# BLE-NTC.net
KiCad netlist of a schematic drawn in Altium Designer
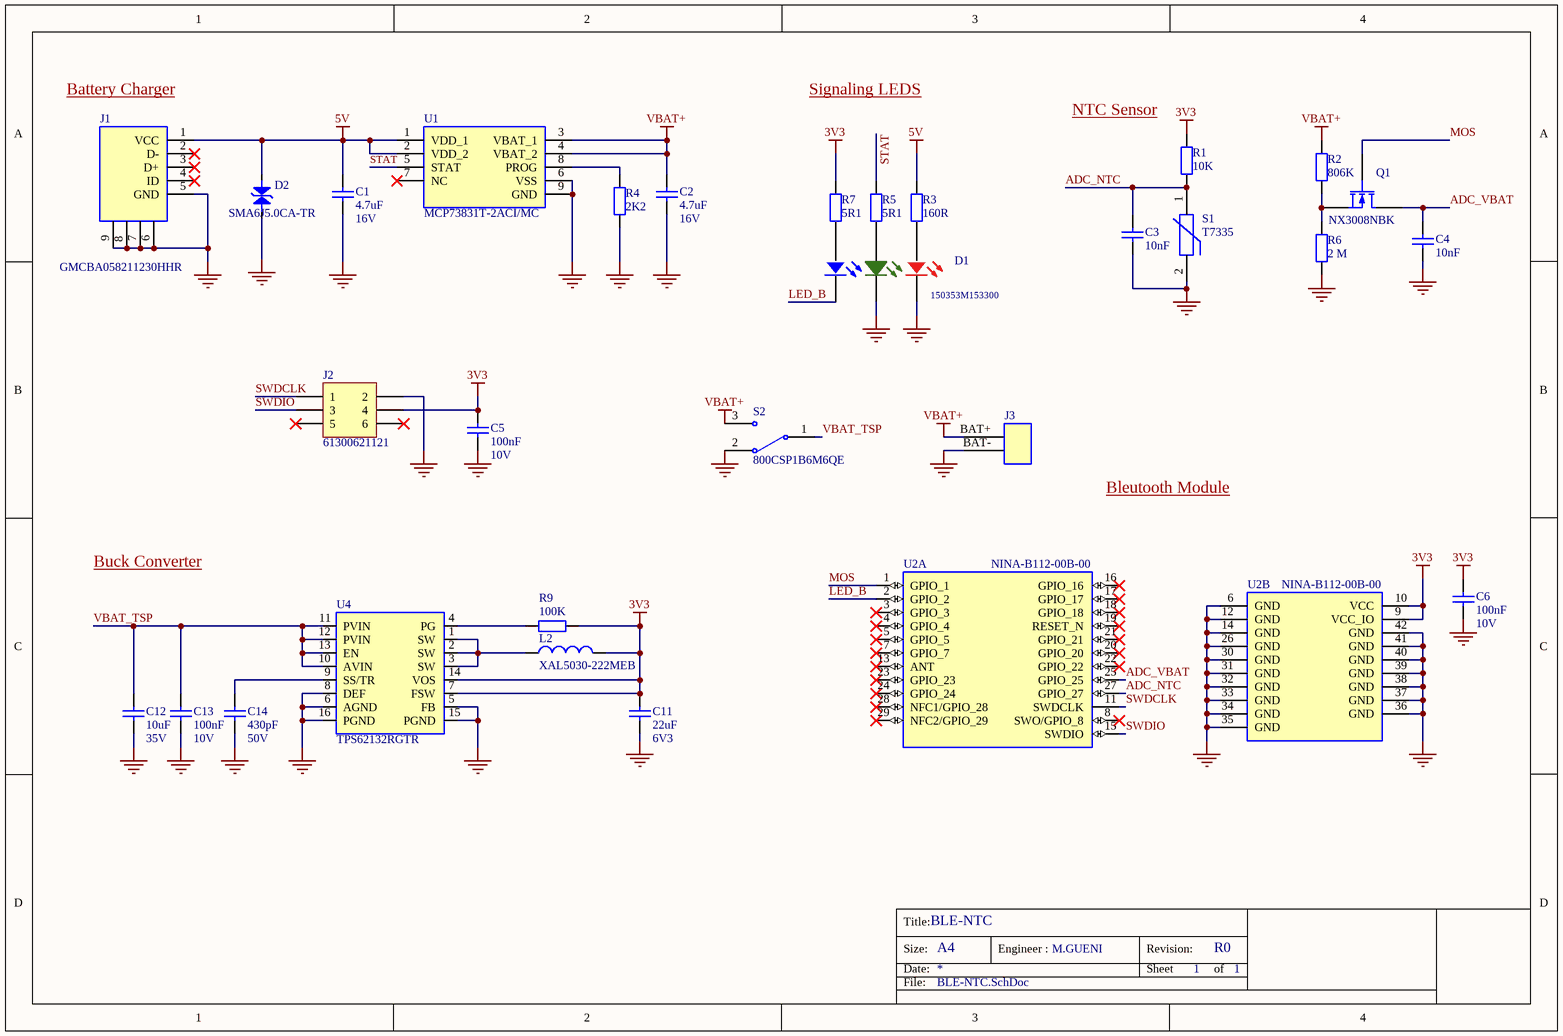
[diagram p0: BLE-NTC.SchDoc]

(export (version "E")
  (design (tool "Eeschema 10.0.6"))
  (components
    (comp (ref "C1")
      (value "Capacitor")
      (footprint "CAPC1608N")
      (fields
        (field (name "PART NUMBER") "CAP-000000047")
        (field (name "VALUE 1") "4.7uF")
        (field (name "VALUE 2") "16V")
      )
      (libsource (lib "Database_Libs1") (part "Capacitor"))
    )
    (comp (ref "C2")
      (value "Capacitor")
      (footprint "CAPC1608N")
      (fields
        (field (name "PART NUMBER") "CAP-000000047")
        (field (name "VALUE 1") "4.7uF")
        (field (name "VALUE 2") "16V")
      )
      (libsource (lib "Database_Libs1") (part "Capacitor"))
    )
    (comp (ref "C3")
      (value "Capacitor")
      (footprint "CAPC1608N")
      (fields (field (name "PART NUMBER") "CAP-000000003") (field (name "VALUE 1") "10nF"))
      (libsource (lib "Database_Libs1") (part "Capacitor"))
    )
    (comp (ref "C4")
      (value "Capacitor")
      (footprint "CAPC1608N")
      (fields (field (name "PART NUMBER") "CAP-000000003") (field (name "VALUE 1") "10nF"))
      (libsource (lib "Database_Libs1") (part "Capacitor"))
    )
    (comp (ref "C5")
      (value "Capacitor")
      (footprint "CAPC1608N")
      (fields
        (field (name "PART NUMBER") "CAP-000000005")
        (field (name "VALUE 1") "100nF")
        (field (name "VALUE 2") "10V")
      )
      (libsource (lib "Database_Libs1") (part "Capacitor"))
    )
    (comp (ref "C6")
      (value "Capacitor")
      (footprint "CAPC1608N")
      (fields
        (field (name "PART NUMBER") "CAP-000000005")
        (field (name "VALUE 1") "100nF")
        (field (name "VALUE 2") "10V")
      )
      (libsource (lib "Database_Libs1") (part "Capacitor"))
    )
    (comp (ref "C11")
      (value "Capacitor")
      (footprint "CAPC1608N")
      (fields
        (field (name "PART NUMBER") "CAP-000000045")
        (field (name "VALUE 1") "22uF")
        (field (name "VALUE 2") "6V3")
      )
      (libsource (lib "Database_Libs1") (part "Capacitor"))
    )
    (comp (ref "C12")
      (value "Capacitor")
      (footprint "CAPC1608N")
      (fields
        (field (name "PART NUMBER") "CAP-000000006")
        (field (name "VALUE 1") "10uF")
        (field (name "VALUE 2") "35V")
      )
      (libsource (lib "Database_Libs1") (part "Capacitor"))
    )
    (comp (ref "C13")
      (value "Capacitor")
      (footprint "CAPC1608N")
      (fields
        (field (name "PART NUMBER") "CAP-000000005")
        (field (name "VALUE 1") "100nF")
        (field (name "VALUE 2") "10V")
      )
      (libsource (lib "Database_Libs1") (part "Capacitor"))
    )
    (comp (ref "C14")
      (value "Capacitor")
      (footprint "CAPC1608N")
      (fields
        (field (name "PART NUMBER") "CAP-000000044")
        (field (name "VALUE 1") "430pF")
        (field (name "VALUE 2") "50V")
      )
      (libsource (lib "Database_Libs1") (part "Capacitor"))
    )
    (comp (ref "D1")
      (value "150353M153300")
      (footprint "150353M153300")
      (fields (field (name "PART NUMBER") "LED-000000004"))
      (libsource (lib "Database_Libs1") (part "150353M153300"))
    )
    (comp (ref "D2")
      (value "SMA6J5.0CA-TR")
      (footprint "SMA6J5.0CA-TR")
      (fields (field (name "PART NUMBER") "TVS-000000006"))
      (libsource (lib "Database_Libs1") (part "TVS0"))
    )
    (comp (ref "J1")
      (value "GMCBA058211230HHR")
      (footprint "GMCBA058211230HHR")
      (fields (field (name "PART NUMBER") "CON-000000037"))
      (libsource (lib "Database_Libs1") (part "USB"))
    )
    (comp (ref "J2")
      (value "61300621121")
      (footprint "HDR2X3")
      (fields (field (name "PART NUMBER") "CON-000000012"))
      (libsource (lib "Database_Libs1") (part "Header 2X3"))
    )
    (comp (ref "J3")
      (value "BAT_PAD")
      (footprint "BAT_PAD")
      (fields (field (name "PART NUMBER") "MIS-000000024"))
      (libsource (lib "Database_Libs1") (part "BAT_PAD"))
    )
    (comp (ref "L2")
      (value "XAL5030-222MEB")
      (footprint "22uh-XAL5030")
      (fields (field (name "PART NUMBER") "IND-000000001"))
      (libsource (lib "Database_Libs1") (part "Inductor"))
    )
    (comp (ref "Q1")
      (value "NX3008NBK")
      (footprint "SOT23-3N")
      (fields (field (name "PART NUMBER") "TRM-000000001"))
      (libsource (lib "Database_Libs1") (part "MOSFET-N-0"))
    )
    (comp (ref "R1")
      (value "Resistor")
      (footprint "RESC1608N")
      (fields (field (name "PART NUMBER") "RES-000000001") (field (name "VALUE 1") "10K"))
      (libsource (lib "Database_Libs1") (part "Resistor"))
    )
    (comp (ref "R2")
      (value "Resistor")
      (footprint "RESC1608N")
      (fields (field (name "PART NUMBER") "RES-00000011s3") (field (name "VALUE 1") "806K"))
      (libsource (lib "Database_Libs1") (part "Resistor"))
    )
    (comp (ref "R3")
      (value "Resistor")
      (footprint "RESC1608N")
      (fields (field (name "PART NUMBER") "RES-000000098") (field (name "VALUE 1") "160R"))
      (libsource (lib "Database_Libs1") (part "Resistor"))
    )
    (comp (ref "R4")
      (value "Resistor")
      (footprint "RESC1608N")
      (fields (field (name "PART NUMBER") "RES-000000009") (field (name "VALUE 1") "2K2"))
      (libsource (lib "") (part "Resistor_1"))
    )
    (comp (ref "R5")
      (value "Resistor")
      (footprint "RESC1608N")
      (fields (field (name "PART NUMBER") "RES-000000097") (field (name "VALUE 1") "5R1"))
      (libsource (lib "Database_Libs1") (part "Resistor"))
    )
    (comp (ref "R6")
      (value "Resistor")
      (footprint "RESC1608N")
      (fields (field (name "PART NUMBER") "RES-00000011d2") (field (name "VALUE 1") "2 M"))
      (libsource (lib "") (part "Resistor_1"))
    )
    (comp (ref "R7")
      (value "Resistor")
      (footprint "RESC1608N")
      (fields (field (name "PART NUMBER") "RES-000000097") (field (name "VALUE 1") "5R1"))
      (libsource (lib "Database_Libs1") (part "Resistor"))
    )
    (comp (ref "R9")
      (value "Resistor")
      (footprint "RESC1608N")
      (fields (field (name "PART NUMBER") "RES-000000038") (field (name "VALUE 1") "100K"))
      (libsource (lib "") (part "Resistor_2"))
    )
    (comp (ref "S1")
      (value "T7335")
      (footprint "T7335D")
      (fields (field (name "PART NUMBER") "MIS-000000023"))
      (libsource (lib "Database_Libs1") (part "T7335"))
    )
    (comp (ref "S2")
      (value "800CSP1B6M6QE")
      (footprint "800CSP1B6M6QE")
      (fields (field (name "PART NUMBER") "SWC-000000006"))
      (libsource (lib "Database_Libs1") (part "800CSP1B6M6QE"))
    )
    (comp (ref "U1")
      (value "MCP73831T-2ACI/MC")
      (footprint "mcp-SON50P300X200X100-9N-D")
      (fields (field (name "PART NUMBER") "ICP-000000011"))
      (libsource (lib "Database_Libs1") (part "MCP73831T-2ACI_MC"))
    )
    (comp (ref "U2")
      (value "NINA-B112-00B-00")
      (footprint "NINAB112")
      (fields (field (name "PART NUMBER") "RFC-000000004"))
      (libsource (lib "Database_Libs1") (part "NINA-B112"))
    )
    (comp (ref "U4")
      (value "TPS62132RGTR")
      (footprint "tps62132")
      (fields (field (name "PART NUMBER") "ICP-000000010"))
      (libsource (lib "Database_Libs1") (part "TPS62132RGTR"))
    )
  )
  (nets
    (net (code "1") (name "/ADC_NTC") (class "Default")
      (node (ref "C3") (pin "2") (pinfunction "2_2") (pintype "passive"))
      (node (ref "R1") (pin "1") (pinfunction "1_1") (pintype "passive"))
      (node (ref "S1") (pin "1") (pinfunction "1_1") (pintype "passive"))
      (node (ref "U2") (pin "27") (pinfunction "GPIO_27_27") (pintype "bidirectional"))
    )
    (net (code "2") (name "/ADC_VBAT") (class "Default")
      (node (ref "C4") (pin "2") (pinfunction "2_2") (pintype "passive"))
      (node (ref "Q1") (pin "3") (pinfunction "D_3") (pintype "passive"))
      (node (ref "U2") (pin "25") (pinfunction "GPIO_25_25") (pintype "bidirectional"))
    )
    (net (code "3") (name "/LED_B") (class "Default")
      (node (ref "D1") (pin "6") (pinfunction "K_6") (pintype "passive"))
      (node (ref "U2") (pin "2") (pinfunction "GPIO_2_2") (pintype "bidirectional"))
    )
    (net (code "4") (name "/MOS") (class "Default")
      (node (ref "Q1") (pin "1") (pinfunction "G_1") (pintype "passive"))
      (node (ref "U2") (pin "1") (pinfunction "GPIO_1_1") (pintype "bidirectional"))
    )
    (net (code "5") (name "/STAT") (class "Default")
      (node (ref "R5") (pin "2") (pinfunction "2_2") (pintype "passive"))
      (node (ref "U1") (pin "5") (pinfunction "STAT_5") (pintype "passive"))
    )
    (net (code "6") (name "/SWDCLK") (class "Default")
      (node (ref "J2") (pin "1") (pinfunction "1_1") (pintype "passive"))
      (node (ref "U2") (pin "11") (pinfunction "SWDCLK_11") (pintype "passive"))
    )
    (net (code "7") (name "/SWDIO") (class "Default")
      (node (ref "J2") (pin "3") (pinfunction "3_3") (pintype "passive"))
      (node (ref "U2") (pin "15") (pinfunction "SWDIO_15") (pintype "bidirectional"))
    )
    (net (code "8") (name "/VBAT_TSP") (class "Default")
      (node (ref "C12") (pin "2") (pinfunction "2_2") (pintype "passive"))
      (node (ref "C13") (pin "2") (pinfunction "2_2") (pintype "passive"))
      (node (ref "S2") (pin "1") (pinfunction "1_1") (pintype "passive"))
      (node (ref "U4") (pin "10") (pinfunction "AVIN_10") (pintype "passive"))
      (node (ref "U4") (pin "11") (pinfunction "PVIN_11") (pintype "passive"))
      (node (ref "U4") (pin "12") (pinfunction "PVIN_12") (pintype "passive"))
      (node (ref "U4") (pin "13") (pinfunction "EN_13") (pintype "passive"))
    )
    (net (code "9") (name "3V3") (class "Default")
      (node (ref "C11") (pin "2") (pinfunction "2_2") (pintype "passive"))
      (node (ref "C5") (pin "2") (pinfunction "2_2") (pintype "passive"))
      (node (ref "C6") (pin "2") (pinfunction "2_2") (pintype "passive"))
      (node (ref "J2") (pin "4") (pinfunction "4_4") (pintype "passive"))
      (node (ref "L2") (pin "2") (pinfunction "2_2") (pintype "passive"))
      (node (ref "R1") (pin "2") (pinfunction "2_2") (pintype "passive"))
      (node (ref "R7") (pin "2") (pinfunction "2_2") (pintype "passive"))
      (node (ref "R9") (pin "2") (pinfunction "2_2") (pintype "passive"))
      (node (ref "U2") (pin "10") (pinfunction "VCC_10") (pintype "power_in"))
      (node (ref "U2") (pin "9") (pinfunction "VCC_IO_9") (pintype "power_in"))
      (node (ref "U4") (pin "14") (pinfunction "VOS_14") (pintype "passive"))
      (node (ref "U4") (pin "7") (pinfunction "FSW_7") (pintype "passive"))
    )
    (net (code "10") (name "5V") (class "Default")
      (node (ref "C1") (pin "1") (pinfunction "1_1") (pintype "passive"))
      (node (ref "D2") (pin "2") (pinfunction "K1A2_2") (pintype "passive"))
      (node (ref "J1") (pin "1") (pinfunction "VCC_1") (pintype "passive"))
      (node (ref "R3") (pin "2") (pinfunction "2_2") (pintype "passive"))
      (node (ref "U1") (pin "1") (pinfunction "VDD_1_1") (pintype "passive"))
      (node (ref "U1") (pin "2") (pinfunction "VDD_2_2") (pintype "passive"))
    )
    (net (code "11") (name "GND") (class "Default")
      (node (ref "C1") (pin "2") (pinfunction "2_2") (pintype "passive"))
      (node (ref "C11") (pin "1") (pinfunction "1_1") (pintype "passive"))
      (node (ref "C12") (pin "1") (pinfunction "1_1") (pintype "passive"))
      (node (ref "C13") (pin "1") (pinfunction "1_1") (pintype "passive"))
      (node (ref "C14") (pin "1") (pinfunction "1_1") (pintype "passive"))
      (node (ref "C2") (pin "2") (pinfunction "2_2") (pintype "passive"))
      (node (ref "C3") (pin "1") (pinfunction "1_1") (pintype "passive"))
      (node (ref "C4") (pin "1") (pinfunction "1_1") (pintype "passive"))
      (node (ref "C5") (pin "1") (pinfunction "1_1") (pintype "passive"))
      (node (ref "C6") (pin "1") (pinfunction "1_1") (pintype "passive"))
      (node (ref "D1") (pin "2") (pinfunction "K_2") (pintype "passive"))
      (node (ref "D1") (pin "4") (pinfunction "K_4") (pintype "passive"))
      (node (ref "D2") (pin "1") (pinfunction "1_1") (pintype "passive"))
      (node (ref "J1") (pin "5") (pinfunction "GND_5") (pintype "passive"))
      (node (ref "J1") (pin "6") (pinfunction "6_6") (pintype "passive"))
      (node (ref "J1") (pin "7") (pinfunction "7_7") (pintype "passive"))
      (node (ref "J1") (pin "8") (pinfunction "Shield_8") (pintype "passive"))
      (node (ref "J1") (pin "9") (pinfunction "9_9") (pintype "passive"))
      (node (ref "J2") (pin "2") (pinfunction "2_2") (pintype "passive"))
      (node (ref "J3") (pin "BAT-") (pinfunction "BAT-_BAT-") (pintype "passive"))
      (node (ref "R4") (pin "2") (pinfunction "2_2") (pintype "passive"))
      (node (ref "R6") (pin "2") (pinfunction "2_2") (pintype "passive"))
      (node (ref "S1") (pin "2") (pinfunction "2_2") (pintype "passive"))
      (node (ref "S2") (pin "2") (pinfunction "2_2") (pintype "passive"))
      (node (ref "U1") (pin "6") (pinfunction "VSS_6") (pintype "passive"))
      (node (ref "U1") (pin "9") (pinfunction "GND_9") (pintype "passive"))
      (node (ref "U2") (pin "12") (pinfunction "GND_12") (pintype "power_in"))
      (node (ref "U2") (pin "14") (pinfunction "GND_14") (pintype "power_in"))
      (node (ref "U2") (pin "26") (pinfunction "GND_26") (pintype "power_in"))
      (node (ref "U2") (pin "30") (pinfunction "GND_30") (pintype "power_in"))
      (node (ref "U2") (pin "31") (pinfunction "GND_31") (pintype "power_in"))
      (node (ref "U2") (pin "32") (pinfunction "GND_32") (pintype "power_in"))
      (node (ref "U2") (pin "33") (pinfunction "GND_33") (pintype "power_in"))
      (node (ref "U2") (pin "34") (pinfunction "GND_34") (pintype "power_in"))
      (node (ref "U2") (pin "35") (pinfunction "GND_35") (pintype "power_in"))
      (node (ref "U2") (pin "36") (pinfunction "GND_36") (pintype "power_in"))
      (node (ref "U2") (pin "37") (pinfunction "GND_37") (pintype "power_in"))
      (node (ref "U2") (pin "38") (pinfunction "GND_38") (pintype "power_in"))
      (node (ref "U2") (pin "39") (pinfunction "GND_39") (pintype "power_in"))
      (node (ref "U2") (pin "40") (pinfunction "GND_40") (pintype "power_in"))
      (node (ref "U2") (pin "41") (pinfunction "GND_41") (pintype "power_in"))
      (node (ref "U2") (pin "42") (pinfunction "GND_42") (pintype "power_in"))
      (node (ref "U2") (pin "6") (pinfunction "GND_6") (pintype "power_in"))
      (node (ref "U4") (pin "15") (pinfunction "PGND_15") (pintype "passive"))
      (node (ref "U4") (pin "16") (pinfunction "PGND_16") (pintype "passive"))
      (node (ref "U4") (pin "5") (pinfunction "FB_5") (pintype "passive"))
      (node (ref "U4") (pin "6") (pinfunction "AGND_6") (pintype "passive"))
      (node (ref "U4") (pin "8") (pinfunction "DEF_8") (pintype "passive"))
    )
    (net (code "12") (name "Net-(D1-A-Pad1)") (class "Default")
      (node (ref "D1") (pin "1") (pinfunction "A_1") (pintype "passive"))
      (node (ref "R3") (pin "1") (pinfunction "1_1") (pintype "passive"))
    )
    (net (code "13") (name "Net-(D1-A-Pad3)") (class "Default")
      (node (ref "D1") (pin "3") (pinfunction "A_3") (pintype "passive"))
      (node (ref "R5") (pin "1") (pinfunction "1_1") (pintype "passive"))
    )
    (net (code "14") (name "Net-(D1-A-Pad5)") (class "Default")
      (node (ref "D1") (pin "5") (pinfunction "A_5") (pintype "passive"))
      (node (ref "R7") (pin "1") (pinfunction "1_1") (pintype "passive"))
    )
    (net (code "15") (name "Net-(L2-Pad1)") (class "Default")
      (node (ref "L2") (pin "1") (pinfunction "1_1") (pintype "passive"))
      (node (ref "U4") (pin "1") (pinfunction "SW_1") (pintype "passive"))
      (node (ref "U4") (pin "2") (pinfunction "SW_2") (pintype "passive"))
      (node (ref "U4") (pin "3") (pinfunction "SW_3") (pintype "passive"))
    )
    (net (code "16") (name "Net-(Q1-S)") (class "Default")
      (node (ref "Q1") (pin "2") (pinfunction "S_2") (pintype "passive"))
      (node (ref "R2") (pin "1") (pinfunction "1_1") (pintype "passive"))
      (node (ref "R6") (pin "1") (pinfunction "1_1") (pintype "passive"))
    )
    (net (code "17") (name "Net-(U1-PROG)") (class "Default")
      (node (ref "R4") (pin "1") (pinfunction "1_1") (pintype "passive"))
      (node (ref "U1") (pin "8") (pinfunction "PROG_8") (pintype "passive"))
    )
    (net (code "18") (name "Net-(U4-PG)") (class "Default")
      (node (ref "R9") (pin "1") (pinfunction "1_1") (pintype "passive"))
      (node (ref "U4") (pin "4") (pinfunction "PG_4") (pintype "passive"))
    )
    (net (code "19") (name "Net-(U4-SS{slash}TR)") (class "Default")
      (node (ref "C14") (pin "2") (pinfunction "2_2") (pintype "passive"))
      (node (ref "U4") (pin "9") (pinfunction "SS/TR_9") (pintype "passive"))
    )
    (net (code "20") (name "VBAT+") (class "Default")
      (node (ref "C2") (pin "1") (pinfunction "1_1") (pintype "passive"))
      (node (ref "J3") (pin "BAT+") (pinfunction "BAT+_BAT+") (pintype "passive"))
      (node (ref "R2") (pin "2") (pinfunction "2_2") (pintype "passive"))
      (node (ref "S2") (pin "3") (pinfunction "3_3") (pintype "passive"))
      (node (ref "U1") (pin "3") (pinfunction "VBAT_1_3") (pintype "passive"))
      (node (ref "U1") (pin "4") (pinfunction "VBAT_2_4") (pintype "passive"))
    )
    (net (code "21") (name "unconnected-(J1-D+-Pad3)") (class "Default")
      (node (ref "J1") (pin "3") (pinfunction "D+_3") (pintype "passive+no_connect"))
    )
    (net (code "22") (name "unconnected-(J1-D--Pad2)") (class "Default")
      (node (ref "J1") (pin "2") (pinfunction "D-_2") (pintype "passive+no_connect"))
    )
    (net (code "23") (name "unconnected-(J1-ID-Pad4)") (class "Default")
      (node (ref "J1") (pin "4") (pinfunction "ID_4") (pintype "passive+no_connect"))
    )
    (net (code "24") (name "unconnected-(J2-Pad5)") (class "Default")
      (node (ref "J2") (pin "5") (pinfunction "5_5") (pintype "passive+no_connect"))
    )
    (net (code "25") (name "unconnected-(J2-Pad6)") (class "Default")
      (node (ref "J2") (pin "6") (pinfunction "6_6") (pintype "passive+no_connect"))
    )
    (net (code "26") (name "unconnected-(U1-NC-Pad7)") (class "Default")
      (node (ref "U1") (pin "7") (pinfunction "NC_7") (pintype "passive+no_connect"))
    )
    (net (code "27") (name "unconnected-(U2A-ANT-Pad13)") (class "Default")
      (node (ref "U2") (pin "13") (pinfunction "ANT_13") (pintype "bidirectional+no_connect"))
    )
    (net (code "28") (name "unconnected-(U2A-GPIO_3-Pad3)") (class "Default")
      (node (ref "U2") (pin "3") (pinfunction "GPIO_3_3") (pintype "bidirectional+no_connect"))
    )
    (net (code "29") (name "unconnected-(U2A-GPIO_4-Pad4)") (class "Default")
      (node (ref "U2") (pin "4") (pinfunction "GPIO_4_4") (pintype "bidirectional+no_connect"))
    )
    (net (code "30") (name "unconnected-(U2A-GPIO_5-Pad5)") (class "Default")
      (node (ref "U2") (pin "5") (pinfunction "GPIO_5_5") (pintype "bidirectional+no_connect"))
    )
    (net (code "31") (name "unconnected-(U2A-GPIO_7-Pad7)") (class "Default")
      (node (ref "U2") (pin "7") (pinfunction "GPIO_7_7") (pintype "bidirectional+no_connect"))
    )
    (net (code "32") (name "unconnected-(U2A-GPIO_16-Pad16)") (class "Default")
      (node (ref "U2") (pin "16") (pinfunction "GPIO_16_16") (pintype "bidirectional+no_connect"))
    )
    (net (code "33") (name "unconnected-(U2A-GPIO_17-Pad17)") (class "Default")
      (node (ref "U2") (pin "17") (pinfunction "GPIO_17_17") (pintype "bidirectional+no_connect"))
    )
    (net (code "34") (name "unconnected-(U2A-GPIO_18-Pad18)") (class "Default")
      (node (ref "U2") (pin "18") (pinfunction "GPIO_18_18") (pintype "bidirectional+no_connect"))
    )
    (net (code "35") (name "unconnected-(U2A-GPIO_20-Pad20)") (class "Default")
      (node (ref "U2") (pin "20") (pinfunction "GPIO_20_20") (pintype "bidirectional+no_connect"))
    )
    (net (code "36") (name "unconnected-(U2A-GPIO_21-Pad21)") (class "Default")
      (node (ref "U2") (pin "21") (pinfunction "GPIO_21_21") (pintype "bidirectional+no_connect"))
    )
    (net (code "37") (name "unconnected-(U2A-GPIO_22-Pad22)") (class "Default")
      (node (ref "U2") (pin "22") (pinfunction "GPIO_22_22") (pintype "bidirectional+no_connect"))
    )
    (net (code "38") (name "unconnected-(U2A-GPIO_23-Pad23)") (class "Default")
      (node (ref "U2") (pin "23") (pinfunction "GPIO_23_23") (pintype "bidirectional+no_connect"))
    )
    (net (code "39") (name "unconnected-(U2A-GPIO_24-Pad24)") (class "Default")
      (node (ref "U2") (pin "24") (pinfunction "GPIO_24_24") (pintype "bidirectional+no_connect"))
    )
    (net (code "40") (name "unconnected-(U2A-NFC1{slash}GPIO_28-Pad28)") (class "Default")
      (node (ref "U2") (pin "28") (pinfunction "NFC1/GPIO_28_28") (pintype "bidirectional+no_connect"))
    )
    (net (code "41") (name "unconnected-(U2A-NFC2{slash}GPIO_29-Pad29)") (class "Default")
      (node (ref "U2") (pin "29") (pinfunction "NFC2/GPIO_29_29") (pintype "bidirectional+no_connect"))
    )
    (net (code "42") (name "unconnected-(U2A-RESET_N-Pad19)") (class "Default")
      (node (ref "U2") (pin "19") (pinfunction "RESET_N_19") (pintype "bidirectional+no_connect"))
    )
    (net (code "43") (name "unconnected-(U2A-SWO{slash}GPIO_8-Pad8)") (class "Default")
      (node (ref "U2") (pin "8") (pinfunction "SWO/GPIO_8_8") (pintype "bidirectional+no_connect"))
    )
  )
)
